# Plataforma_soldadora.net
KiCad netlist of a schematic drawn in EAGLE
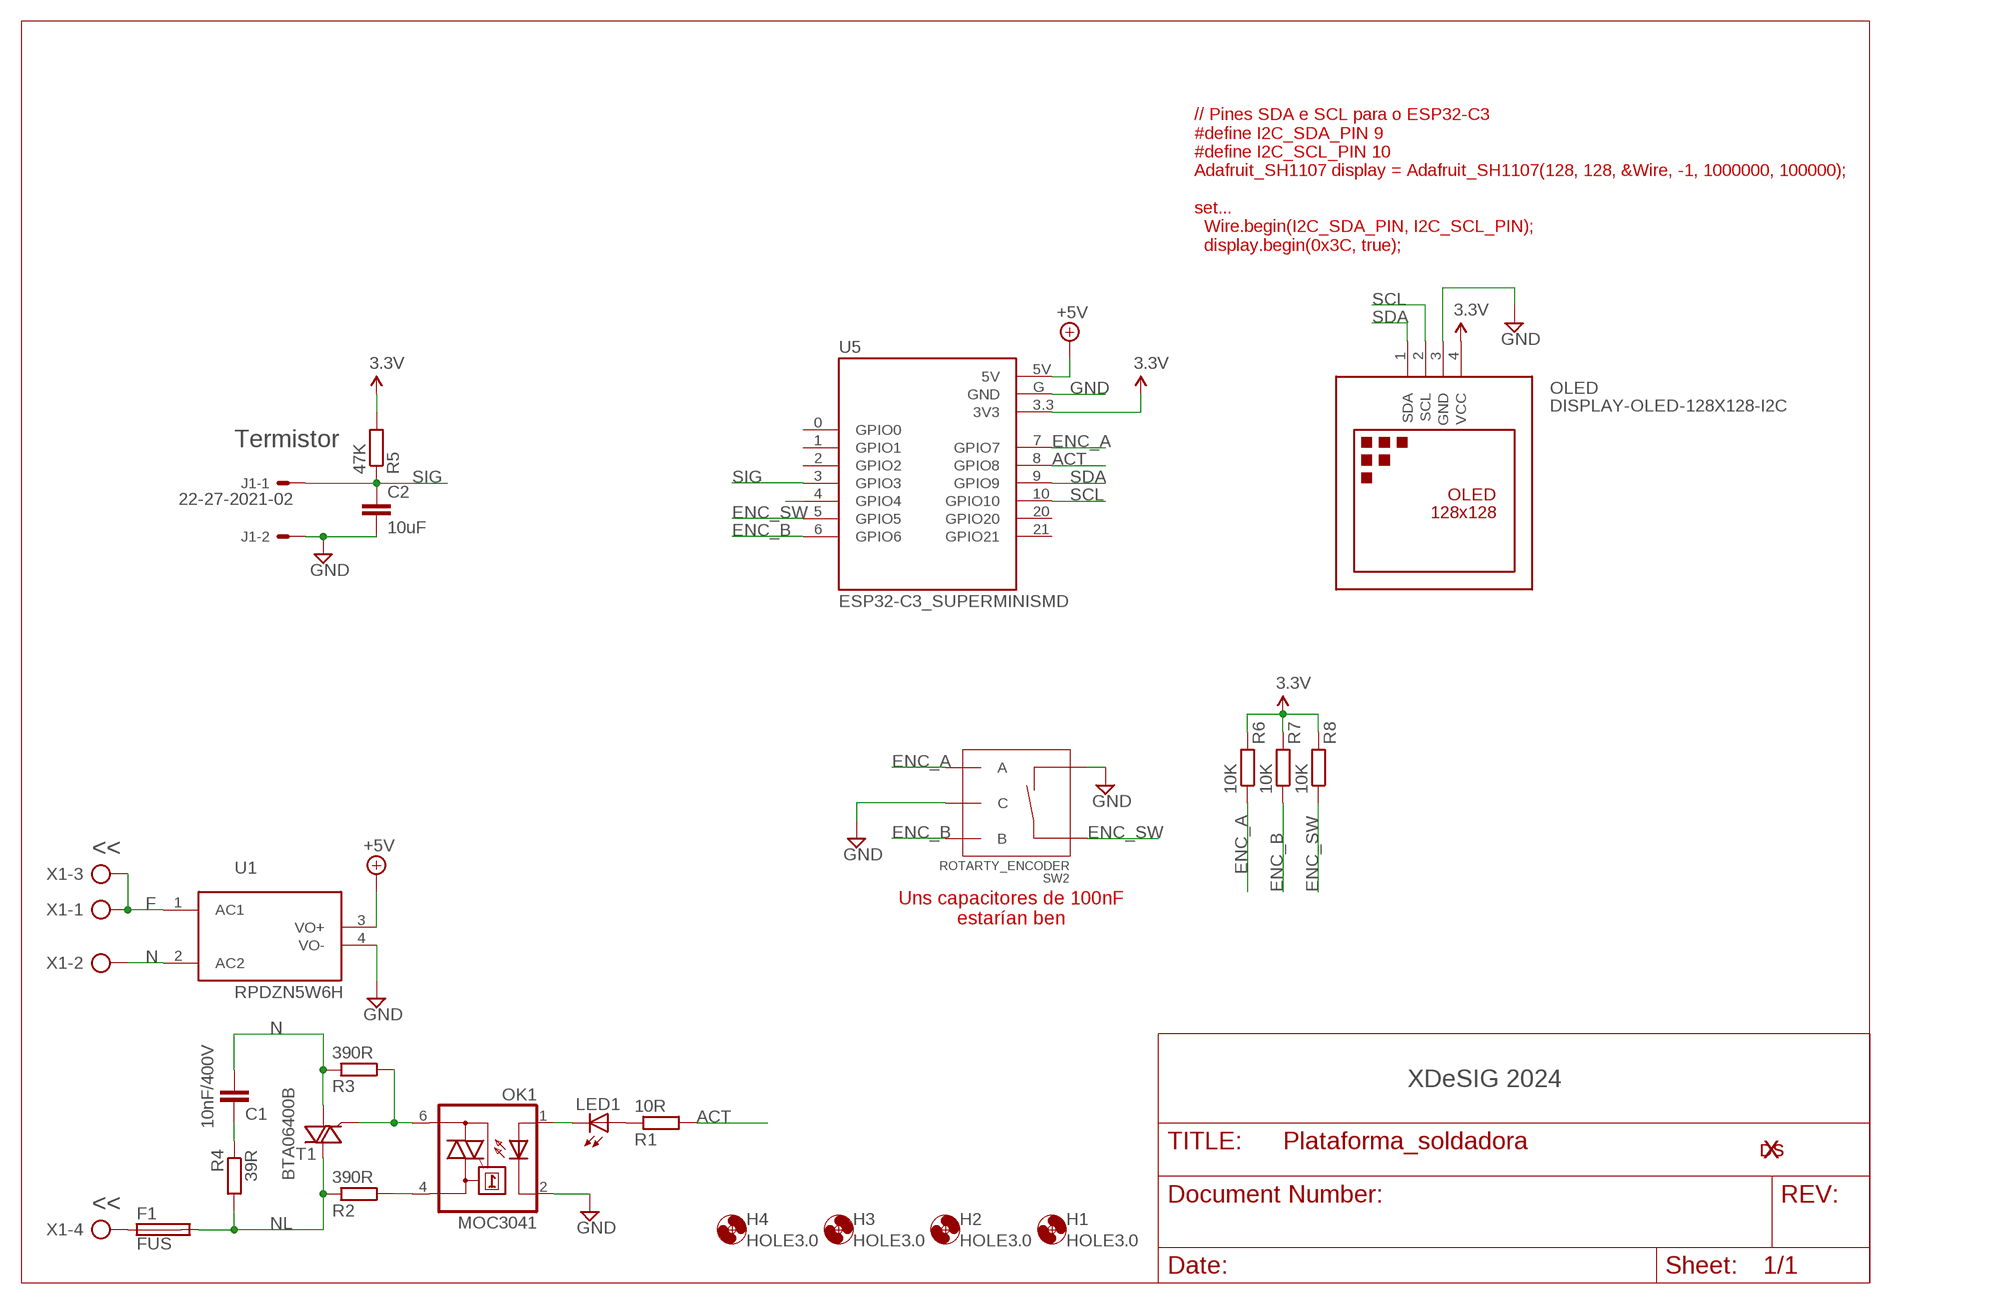
[diagram p0: schematic, sheet 1]

(export (version "E")
  (design (tool "Eeschema 10.0.6"))
  (components
    (comp (ref "C1")
      (value "10nF/400V")
      (footprint "eagle-import:C075-042X103")
      (libsource (lib "eagle-import") (part "C-EU075-042X103"))
    )
    (comp (ref "C2")
      (value "10uF")
      (footprint "eagle-import:C1206K")
      (libsource (lib "eagle-import") (part "C-EUC1206K"))
    )
    (comp (ref "F1")
      (value "FUS")
      (footprint "eagle-import:TE5")
      (libsource (lib "eagle-import") (part "FUSETE5"))
    )
    (comp (ref "H1")
      (value "HOLE3.0")
      (footprint "eagle-import:HOLES_3,0")
      (libsource (lib "eagle-import") (part "HOLES_MOUNT-HOLE3.0"))
    )
    (comp (ref "H2")
      (value "HOLE3.0")
      (footprint "eagle-import:HOLES_3,0")
      (libsource (lib "eagle-import") (part "HOLES_MOUNT-HOLE3.0"))
    )
    (comp (ref "H3")
      (value "HOLE3.0")
      (footprint "eagle-import:HOLES_3,0")
      (libsource (lib "eagle-import") (part "HOLES_MOUNT-HOLE3.0"))
    )
    (comp (ref "H4")
      (value "HOLE3.0")
      (footprint "eagle-import:HOLES_3,0")
      (libsource (lib "eagle-import") (part "HOLES_MOUNT-HOLE3.0"))
    )
    (comp (ref "J1")
      (value "22-27-2021-02")
      (footprint "eagle-import:6410-02")
      (libsource (lib "eagle-import") (part "22-?-0227-2021"))
    )
    (comp (ref "LED1")
      (value "LED3MM")
      (footprint "eagle-import:LED3MM")
      (libsource (lib "eagle-import") (part "LED3MM"))
    )
    (comp (ref "OK1")
      (value "MOC3041")
      (footprint "eagle-import:DIL06")
      (fields (field (name "MF") "VISHAY/TELEFUNKEN") (field (name "MPN") "IL410"))
      (libsource (lib "eagle-import") (part "IL410"))
    )
    (comp (ref "OLED")
      (value "DISPLAY-OLED-128X128-I2C")
      (footprint "eagle-import:DISPLAY-OLED-128X128-I2C")
      (libsource (lib "eagle-import") (part "DISPLAY-OLED-128X128-I2C"))
    )
    (comp (ref "R1")
      (value "10R")
      (footprint "eagle-import:R0603")
      (libsource (lib "eagle-import") (part "R-EU_R0603"))
    )
    (comp (ref "R2")
      (value "390R")
      (footprint "eagle-import:0204_7")
      (libsource (lib "eagle-import") (part "R-EU_0204/7"))
    )
    (comp (ref "R3")
      (value "390R")
      (footprint "eagle-import:0204_7")
      (libsource (lib "eagle-import") (part "R-EU_0204/7"))
    )
    (comp (ref "R4")
      (value "39R")
      (footprint "eagle-import:0204_7")
      (libsource (lib "eagle-import") (part "R-EU_0204/7"))
    )
    (comp (ref "R5")
      (value "47K")
      (footprint "eagle-import:R0603")
      (libsource (lib "eagle-import") (part "R-EU_R0603"))
    )
    (comp (ref "R6")
      (value "10K")
      (footprint "eagle-import:R0603")
      (libsource (lib "eagle-import") (part "R-EU_R0603"))
    )
    (comp (ref "R7")
      (value "10K")
      (footprint "eagle-import:R0603")
      (libsource (lib "eagle-import") (part "R-EU_R0603"))
    )
    (comp (ref "R8")
      (value "10K")
      (footprint "eagle-import:R0603")
      (libsource (lib "eagle-import") (part "R-EU_R0603"))
    )
    (comp (ref "SW2")
      (value "ROTARTY_ENCODER")
      (footprint "eagle-import:ROTARY_ENC_PLAIN")
      (libsource (lib "eagle-import") (part "ROTARTY_ENCODER"))
    )
    (comp (ref "T1")
      (value "BTA06400B")
      (footprint "eagle-import:TO220AB")
      (libsource (lib "eagle-import") (part "BT136"))
    )
    (comp (ref "U$2")
      (value "XDESIG_XDESIG5MM")
      (footprint "eagle-import:XDESIG_XDESIG_CU")
      (libsource (lib "eagle-import") (part "XDESIG_XDESIG5MM"))
    )
    (comp (ref "U$3")
      (value "XDESIG_XDESIG21")
      (footprint "eagle-import:XDESIG_XDESIG")
      (libsource (lib "eagle-import") (part "XDESIG_XDESIG21"))
    )
    (comp (ref "U1")
      (value "RPDZN5W6H")
      (footprint "eagle-import:RPDZN5W6H")
      (libsource (lib "eagle-import") (part "RPDZN5W6H"))
    )
    (comp (ref "U5")
      (value "ESP32-C3_SUPERMINISMD")
      (footprint "eagle-import:MODULE_ESP-C3_SUPERMINI_SMD")
      (libsource (lib "eagle-import") (part "ESP32-C3_SUPERMINISMD"))
    )
    (comp (ref "X1")
      (value "AK500/4-H")
      (footprint "eagle-import:AK500_4-H")
      (libsource (lib "eagle-import") (part "AK500/4-H"))
    )
  )
  (nets
    (net (code "1") (name "+5V") (class "Default")
      (node (ref "U1") (pin "3") (pinfunction "VO+_3") (pintype "bidirectional"))
      (node (ref "U5") (pin "5V") (pinfunction "5V_5V") (pintype "power_in"))
    )
    (net (code "2") (name "/ACT") (class "Default")
      (node (ref "R1") (pin "2") (pinfunction "2_2") (pintype "passive"))
      (node (ref "U5") (pin "8") (pinfunction "GPIO8_8") (pintype "bidirectional"))
    )
    (net (code "3") (name "/ENC_A") (class "Default")
      (node (ref "R6") (pin "1") (pinfunction "1_1") (pintype "passive"))
      (node (ref "SW2") (pin "A") (pinfunction "A_A") (pintype "bidirectional"))
      (node (ref "U5") (pin "7") (pinfunction "GPIO7_7") (pintype "bidirectional"))
    )
    (net (code "4") (name "/ENC_B") (class "Default")
      (node (ref "R7") (pin "1") (pinfunction "1_1") (pintype "passive"))
      (node (ref "SW2") (pin "B") (pinfunction "B_B") (pintype "bidirectional"))
      (node (ref "U5") (pin "6") (pinfunction "GPIO6_6") (pintype "bidirectional"))
    )
    (net (code "5") (name "/ENC_SW") (class "Default")
      (node (ref "R8") (pin "1") (pinfunction "1_1") (pintype "passive"))
      (node (ref "SW2") (pin "SW+") (pinfunction "SW+_SW+") (pintype "bidirectional"))
      (node (ref "U5") (pin "5") (pinfunction "GPIO5_5") (pintype "bidirectional"))
    )
    (net (code "6") (name "/F") (class "Default")
      (node (ref "U1") (pin "1") (pinfunction "AC1_1") (pintype "bidirectional"))
      (node (ref "X1") (pin "1") (pinfunction "KL_1") (pintype "passive"))
      (node (ref "X1") (pin "3") (pinfunction "KL_3") (pintype "passive"))
    )
    (net (code "7") (name "/N") (class "Default")
      (node (ref "C1") (pin "2") (pinfunction "2_2") (pintype "passive"))
      (node (ref "R3") (pin "1") (pinfunction "1_1") (pintype "passive"))
      (node (ref "T1") (pin "1") (pinfunction "A1_1") (pintype "passive"))
      (node (ref "U1") (pin "2") (pinfunction "AC2_2") (pintype "bidirectional"))
      (node (ref "X1") (pin "2") (pinfunction "KL_2") (pintype "passive"))
    )
    (net (code "8") (name "/NL") (class "Default")
      (node (ref "F1") (pin "2") (pinfunction "2_2") (pintype "passive"))
      (node (ref "R2") (pin "1") (pinfunction "1_1") (pintype "passive"))
      (node (ref "R4") (pin "2") (pinfunction "2_2") (pintype "passive"))
      (node (ref "T1") (pin "2") (pinfunction "A2_2") (pintype "passive"))
    )
    (net (code "9") (name "/SCL") (class "Default")
      (node (ref "OLED") (pin "2") (pinfunction "SCL_2") (pintype "bidirectional"))
      (node (ref "U5") (pin "10") (pinfunction "GPIO10_10") (pintype "bidirectional"))
    )
    (net (code "10") (name "/SDA") (class "Default")
      (node (ref "OLED") (pin "1") (pinfunction "SDA_1") (pintype "bidirectional"))
      (node (ref "U5") (pin "9") (pinfunction "GPIO9_9") (pintype "bidirectional"))
    )
    (net (code "11") (name "/SIG") (class "Default")
      (node (ref "C2") (pin "1") (pinfunction "1_1") (pintype "passive"))
      (node (ref "J1") (pin "1") (pinfunction "S_1") (pintype "passive"))
      (node (ref "R5") (pin "1") (pinfunction "1_1") (pintype "passive"))
      (node (ref "U5") (pin "3") (pinfunction "GPIO3_3") (pintype "bidirectional"))
    )
    (net (code "12") (name "3.3V") (class "Default")
      (node (ref "OLED") (pin "4") (pinfunction "VCC_4") (pintype "power_in"))
      (node (ref "R5") (pin "2") (pinfunction "2_2") (pintype "passive"))
      (node (ref "R6") (pin "2") (pinfunction "2_2") (pintype "passive"))
      (node (ref "R7") (pin "2") (pinfunction "2_2") (pintype "passive"))
      (node (ref "R8") (pin "2") (pinfunction "2_2") (pintype "passive"))
      (node (ref "U5") (pin "3.3") (pinfunction "3V3_3.3") (pintype "power_in"))
    )
    (net (code "13") (name "GND") (class "Default")
      (node (ref "C2") (pin "2") (pinfunction "2_2") (pintype "passive"))
      (node (ref "J1") (pin "2") (pinfunction "S_2") (pintype "passive"))
      (node (ref "OK1") (pin "2") (pinfunction "C_2") (pintype "passive"))
      (node (ref "OLED") (pin "3") (pinfunction "GND_3") (pintype "power_in"))
      (node (ref "SW2") (pin "C") (pinfunction "C_C") (pintype "bidirectional"))
      (node (ref "SW2") (pin "SW-") (pinfunction "SW-_SW-") (pintype "bidirectional"))
      (node (ref "U1") (pin "4") (pinfunction "VO-_4") (pintype "bidirectional"))
      (node (ref "U5") (pin "G") (pinfunction "GND_G") (pintype "power_in"))
    )
    (net (code "14") (name "Net-(C1-Pad1)") (class "Default")
      (node (ref "C1") (pin "1") (pinfunction "1_1") (pintype "passive"))
      (node (ref "R4") (pin "1") (pinfunction "1_1") (pintype "passive"))
    )
    (net (code "15") (name "Net-(LED1-C)") (class "Default")
      (node (ref "LED1") (pin "K") (pinfunction "C_K") (pintype "passive"))
      (node (ref "OK1") (pin "1") (pinfunction "A_1") (pintype "passive"))
    )
    (net (code "16") (name "Net-(LED1-PadA)") (class "Default")
      (node (ref "LED1") (pin "A") (pinfunction "A_A") (pintype "passive"))
      (node (ref "R1") (pin "1") (pinfunction "1_1") (pintype "passive"))
    )
    (net (code "17") (name "Net-(OK1-A1)") (class "Default")
      (node (ref "OK1") (pin "4") (pinfunction "A1_4") (pintype "passive"))
      (node (ref "R2") (pin "2") (pinfunction "2_2") (pintype "passive"))
    )
    (net (code "18") (name "Net-(OK1-A2)") (class "Default")
      (node (ref "OK1") (pin "6") (pinfunction "A2_6") (pintype "passive"))
      (node (ref "R3") (pin "2") (pinfunction "2_2") (pintype "passive"))
      (node (ref "T1") (pin "3") (pinfunction "G_3") (pintype "passive"))
    )
    (net (code "19") (name "Net-(X1D-KL)") (class "Default")
      (node (ref "F1") (pin "1") (pinfunction "1_1") (pintype "passive"))
      (node (ref "X1") (pin "4") (pinfunction "KL_4") (pintype "passive"))
    )
    (net (code "20") (name "unconnected-(U5-GPIO0-Pad0)") (class "Default")
      (node (ref "U5") (pin "0") (pinfunction "GPIO0_0") (pintype "bidirectional"))
    )
    (net (code "21") (name "unconnected-(U5-GPIO1-Pad1)") (class "Default")
      (node (ref "U5") (pin "1") (pinfunction "GPIO1_1") (pintype "bidirectional"))
    )
    (net (code "22") (name "unconnected-(U5-GPIO2-Pad2)") (class "Default")
      (node (ref "U5") (pin "2") (pinfunction "GPIO2_2") (pintype "bidirectional"))
    )
    (net (code "23") (name "unconnected-(U5-GPIO4-Pad4)") (class "Default")
      (node (ref "U5") (pin "4") (pinfunction "GPIO4_4") (pintype "bidirectional"))
    )
    (net (code "24") (name "unconnected-(U5-GPIO20-Pad20)") (class "Default")
      (node (ref "U5") (pin "20") (pinfunction "GPIO20_20") (pintype "bidirectional"))
    )
    (net (code "25") (name "unconnected-(U5-GPIO21-Pad21)") (class "Default")
      (node (ref "U5") (pin "21") (pinfunction "GPIO21_21") (pintype "bidirectional"))
    )
  )
)
